# OSP_Carrier_V8_USB.net
KiCad netlist of a schematic drawn in Altium Designer
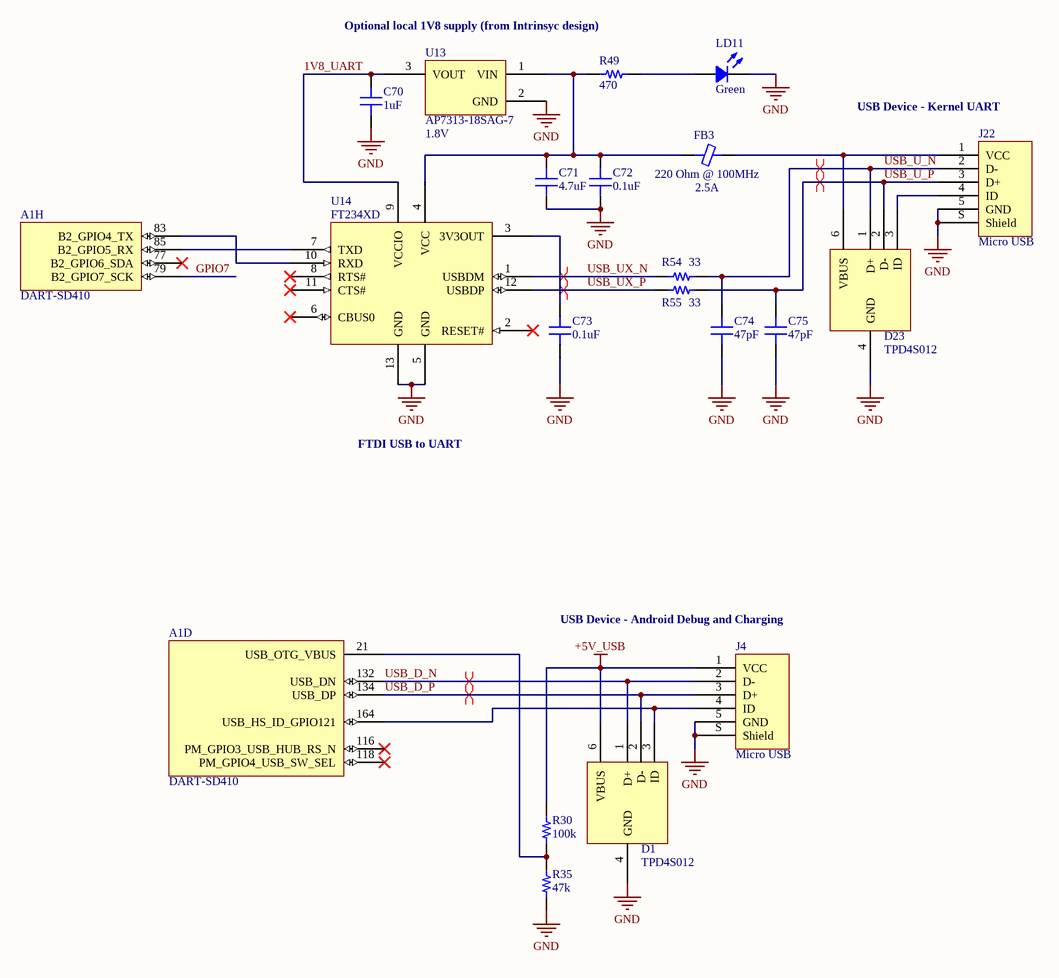
[diagram p0: OSP_Carrier_V8_USB.SchDoc]

(export (version "E")
  (design (tool "Eeschema 10.0.6"))
  (components
    (comp (ref "A1")
      (value "DART-SD410")
      (footprint "DART-SD410")
      (description "Variscite DART-SD410 System on Module")
      (libsource (lib "DART-SD410") (part "DART-SD410"))
    )
    (comp (ref "C70")
      (value "1uF")
      (footprint "CAP 0603/1608")
      (description "CAP CER 1UF 25V X7R 0603")
      (fields
        (field (name "PART NUMBER") "C1608X7R1E105K080AB")
        (field (name "MANUFACTURER") "TDK Corporation")
      )
      (libsource (lib "Celestial Library Database") (part "Capacitor"))
    )
    (comp (ref "C71")
      (value "4.7uF")
      (footprint "CAP 0402/1005")
      (description "CAP CER 4.7UF 10V X5R 0402")
      (fields
        (field (name "PART NUMBER") "C1005X5R1A475K050BC")
        (field (name "MANUFACTURER") "TDK Corporation")
      )
      (libsource (lib "Celestial Library Database") (part "Capacitor"))
    )
    (comp (ref "C72")
      (value "0.1uF")
      (footprint "CAP 0402/1005")
      (description "CAP CER 0.1UF 50V X7R 0402")
      (fields
        (field (name "PART NUMBER") "C1005X7R1H104K050BB")
        (field (name "MANUFACTURER") "TDK Corporation")
      )
      (libsource (lib "Celestial Library Database") (part "Capacitor"))
    )
    (comp (ref "C73")
      (value "0.1uF")
      (footprint "CAP 0402/1005")
      (description "CAP CER 0.1UF 50V X7R 0402")
      (fields
        (field (name "PART NUMBER") "C1005X7R1H104K050BB")
        (field (name "MANUFACTURER") "TDK Corporation")
      )
      (libsource (lib "Celestial Library Database") (part "Capacitor"))
    )
    (comp (ref "C74")
      (value "47pF")
      (footprint "CAP 0402/1005")
      (description "CAP CER 47PF 50V C0G 0402")
      (fields
        (field (name "PART NUMBER") "C1005C0G1H470G050BA")
        (field (name "MANUFACTURER") "TDK Corporation")
      )
      (libsource (lib "Celestial Library Database") (part "Capacitor"))
    )
    (comp (ref "C75")
      (value "47pF")
      (footprint "CAP 0402/1005")
      (description "CAP CER 47PF 50V C0G 0402")
      (fields
        (field (name "PART NUMBER") "C1005C0G1H470G050BA")
        (field (name "MANUFACTURER") "TDK Corporation")
      )
      (libsource (lib "Celestial Library Database") (part "Capacitor"))
    )
    (comp (ref "D1")
      (value "TPD4S012")
      (footprint "TI_SON6")
      (description "TI TPD4S012 USB ESD Protection")
      (libsource (lib "OSP_Symbols") (part "TI_TPD4S012"))
    )
    (comp (ref "D23")
      (value "TPD4S012")
      (footprint "TI_SON6")
      (description "TI TPD4S012 USB ESD Protection")
      (libsource (lib "OSP_Symbols") (part "TI_TPD4S012"))
    )
    (comp (ref "FB3")
      (value "220 Ohm @ 100MHz")
      (footprint "FER 0603/1608")
      (description "FERRITE CHIP 220 OHM 2500MA 0603")
      (fields
        (field (name "PART NUMBER") "CIS10P221NC")
        (field (name "MANUFACTURER") "Samsung Electro-Mechanics America, Inc.")
        (field (name "CURRENT RATING") "2.5A")
      )
      (libsource (lib "Celestial Library Database") (part "Ferrite Chip"))
    )
    (comp (ref "J4")
      (value "Micro USB")
      (footprint "FCI USB 10118193-0001LF")
      (description "CONN USB MICRO B RECPT SMT R/A")
      (fields (field (name "PART NUMBER") "10118193-0001LF"))
      (libsource (lib "Celestial Library Database") (part "USB 2.0 Type B Micro"))
    )
    (comp (ref "J22")
      (value "Micro USB")
      (footprint "FCI USB 10118193-0001LF")
      (description "CONN USB MICRO B RECPT SMT R/A")
      (fields (field (name "PART NUMBER") "10118193-0001LF"))
      (libsource (lib "Celestial Library Database") (part "USB 2.0 Type B Micro"))
    )
    (comp (ref "LD11")
      (value "Green")
      (footprint "LED 0603/1608 GREEN")
      (description "LED GREEN CLEAR 0603 SMD")
      (fields (field (name "PART NUMBER") "LTST-C191KGKT") (field (name "MANUFACTURER") "Lite-On Inc."))
      (libsource (lib "Celestial Library Database") (part "LED"))
    )
    (comp (ref "R30")
      (value "100k")
      (footprint "RES 0402/1005")
      (description "RES SMD 100K OHM 1% 1/10W 0402")
      (fields
        (field (name "PART NUMBER") "ERJ-2RKF1003X")
        (field (name "MANUFACTURER") "Panasonic Electronic Components")
      )
      (libsource (lib "Celestial Library Database") (part "Resistor"))
    )
    (comp (ref "R35")
      (value "47k")
      (footprint "RES 0402/1005")
      (description "RES SMD 47K OHM 1% 1/10W 0402")
      (fields
        (field (name "PART NUMBER") "ERJ-2RKF4702X")
        (field (name "MANUFACTURER") "Panasonic Electronic Components")
      )
      (libsource (lib "Celestial Library Database") (part "Resistor"))
    )
    (comp (ref "R49")
      (value "470")
      (footprint "RES 0402/1005")
      (description "RES SMD 470 OHM 1% 1/10W 0402")
      (fields
        (field (name "PART NUMBER") "ERJ-2RKF4700X")
        (field (name "MANUFACTURER") "Panasonic Electronic Components")
      )
      (libsource (lib "Celestial Library Database") (part "Resistor"))
    )
    (comp (ref "R54")
      (value "33")
      (footprint "RES 0402/1005")
      (description "RES SMD 33 OHM 1% 1/10W 0402")
      (fields
        (field (name "PART NUMBER") "ERJ-2RKF33R0X")
        (field (name "MANUFACTURER") "Panasonic Electronic Components")
      )
      (libsource (lib "Celestial Library Database") (part "Resistor"))
    )
    (comp (ref "R55")
      (value "33")
      (footprint "RES 0402/1005")
      (description "RES SMD 33 OHM 1% 1/10W 0402")
      (fields
        (field (name "PART NUMBER") "ERJ-2RKF33R0X")
        (field (name "MANUFACTURER") "Panasonic Electronic Components")
      )
      (libsource (lib "Celestial Library Database") (part "Resistor"))
    )
    (comp (ref "U13")
      (value "AP7313-18SAG-7")
      (footprint "DIODES SOT-23-3")
      (description "IC REG LDO 1.8V 0.15A SOT23-3")
      (fields (field (name "MANUFACTURER") "Diodes Incorporated") (field (name "VOLTAGE - OUTPUT") "1.8V"))
      (libsource (lib "Celestial Library Database") (part "Diodes Inc AP7313"))
    )
    (comp (ref "U14")
      (value "FT234XD")
      (footprint "FTDI_DFN12")
      (description "FTDI FT234XD USB to UART")
      (libsource (lib "OSP_Symbols") (part "FTDI_FT234XD"))
    )
  )
  (nets
    (net (code "1") (name "+5V_USB") (class "Default")
      (node (ref "D1") (pin "6") (pinfunction "VBUS_6") (pintype "passive"))
      (node (ref "J4") (pin "1") (pinfunction "VCC_1") (pintype "passive"))
      (node (ref "R30") (pin "2") (pinfunction "2_2") (pintype "passive"))
    )
    (net (code "2") (name "/1V8_UART") (class "Default")
      (node (ref "C70") (pin "2") (pinfunction "2_2") (pintype "passive"))
      (node (ref "U13") (pin "3") (pinfunction "VOUT_3") (pintype "passive"))
      (node (ref "U14") (pin "9") (pinfunction "VCCIO_9") (pintype "power_in"))
    )
    (net (code "3") (name "/GPIO7") (class "Default")
      (node (ref "A1") (pin "79") (pinfunction "B2_GPIO7_SCK_79") (pintype "bidirectional"))
    )
    (net (code "4") (name "/USB_D_N") (class "Default")
      (node (ref "A1") (pin "132") (pinfunction "USB_DN_132") (pintype "bidirectional"))
      (node (ref "D1") (pin "1") (pinfunction "D+_1") (pintype "passive"))
      (node (ref "J4") (pin "2") (pinfunction "D-_2") (pintype "passive"))
    )
    (net (code "5") (name "/USB_D_P") (class "Default")
      (node (ref "A1") (pin "134") (pinfunction "USB_DP_134") (pintype "bidirectional"))
      (node (ref "D1") (pin "2") (pinfunction "D-_2") (pintype "passive"))
      (node (ref "J4") (pin "3") (pinfunction "D+_3") (pintype "passive"))
    )
    (net (code "6") (name "/USB_UX_N") (class "Default")
      (node (ref "R54") (pin "1") (pinfunction "1_1") (pintype "passive"))
      (node (ref "U14") (pin "1") (pinfunction "USBDM_1") (pintype "bidirectional"))
    )
    (net (code "7") (name "/USB_UX_P") (class "Default")
      (node (ref "R55") (pin "1") (pinfunction "1_1") (pintype "passive"))
      (node (ref "U14") (pin "12") (pinfunction "USBDP_12") (pintype "bidirectional"))
    )
    (net (code "8") (name "/USB_U_N") (class "Default")
      (node (ref "C74") (pin "2") (pinfunction "2_2") (pintype "passive"))
      (node (ref "D23") (pin "1") (pinfunction "D+_1") (pintype "passive"))
      (node (ref "J22") (pin "2") (pinfunction "D-_2") (pintype "passive"))
      (node (ref "R54") (pin "2") (pinfunction "2_2") (pintype "passive"))
    )
    (net (code "9") (name "/USB_U_P") (class "Default")
      (node (ref "C75") (pin "2") (pinfunction "2_2") (pintype "passive"))
      (node (ref "D23") (pin "2") (pinfunction "D-_2") (pintype "passive"))
      (node (ref "J22") (pin "3") (pinfunction "D+_3") (pintype "passive"))
      (node (ref "R55") (pin "2") (pinfunction "2_2") (pintype "passive"))
    )
    (net (code "10") (name "GND") (class "Default")
      (node (ref "C70") (pin "1") (pinfunction "1_1") (pintype "passive"))
      (node (ref "C71") (pin "1") (pinfunction "1_1") (pintype "passive"))
      (node (ref "C72") (pin "1") (pinfunction "1_1") (pintype "passive"))
      (node (ref "C73") (pin "1") (pinfunction "1_1") (pintype "passive"))
      (node (ref "C74") (pin "1") (pinfunction "1_1") (pintype "passive"))
      (node (ref "C75") (pin "1") (pinfunction "1_1") (pintype "passive"))
      (node (ref "D1") (pin "4") (pinfunction "GND_4") (pintype "passive"))
      (node (ref "D23") (pin "4") (pinfunction "GND_4") (pintype "passive"))
      (node (ref "J22") (pin "5") (pinfunction "GND_5") (pintype "passive"))
      (node (ref "J22") (pin "S") (pinfunction "Shield_S") (pintype "passive"))
      (node (ref "J4") (pin "5") (pinfunction "GND_5") (pintype "passive"))
      (node (ref "J4") (pin "S") (pinfunction "Shield_S") (pintype "passive"))
      (node (ref "LD11") (pin "2") (pinfunction "2_2") (pintype "passive"))
      (node (ref "R35") (pin "1") (pinfunction "1_1") (pintype "passive"))
      (node (ref "U13") (pin "2") (pinfunction "GND_2") (pintype "passive"))
      (node (ref "U14") (pin "13") (pinfunction "GND_13") (pintype "power_in"))
      (node (ref "U14") (pin "5") (pinfunction "GND_5") (pintype "power_in"))
    )
    (net (code "11") (name "Net-(A1D-USB_HS_ID_GPIO121)") (class "Default")
      (node (ref "A1") (pin "164") (pinfunction "USB_HS_ID_GPIO121_164") (pintype "bidirectional"))
      (node (ref "D1") (pin "3") (pinfunction "ID_3") (pintype "passive"))
      (node (ref "J4") (pin "4") (pinfunction "ID_4") (pintype "passive"))
    )
    (net (code "12") (name "Net-(A1D-USB_OTG_VBUS)") (class "Default")
      (node (ref "A1") (pin "21") (pinfunction "USB_OTG_VBUS_21") (pintype "power_in"))
      (node (ref "R30") (pin "1") (pinfunction "1_1") (pintype "passive"))
      (node (ref "R35") (pin "2") (pinfunction "2_2") (pintype "passive"))
    )
    (net (code "13") (name "Net-(A1H-B2_GPIO4_TX)") (class "Default")
      (node (ref "A1") (pin "83") (pinfunction "B2_GPIO4_TX_83") (pintype "bidirectional"))
      (node (ref "U14") (pin "10") (pinfunction "RXD_10") (pintype "input"))
    )
    (net (code "14") (name "Net-(A1H-B2_GPIO5_RX)") (class "Default")
      (node (ref "A1") (pin "85") (pinfunction "B2_GPIO5_RX_85") (pintype "bidirectional"))
      (node (ref "U14") (pin "7") (pinfunction "TXD_7") (pintype "output"))
    )
    (net (code "15") (name "Net-(D23-ID)") (class "Default")
      (node (ref "D23") (pin "3") (pinfunction "ID_3") (pintype "passive"))
      (node (ref "J22") (pin "4") (pinfunction "ID_4") (pintype "passive"))
    )
    (net (code "16") (name "Net-(D23-VBUS)") (class "Default")
      (node (ref "D23") (pin "6") (pinfunction "VBUS_6") (pintype "passive"))
      (node (ref "FB3") (pin "2") (pinfunction "2_2") (pintype "passive"))
      (node (ref "J22") (pin "1") (pinfunction "VCC_1") (pintype "passive"))
    )
    (net (code "17") (name "Net-(LD11-Pad1)") (class "Default")
      (node (ref "LD11") (pin "1") (pinfunction "1_1") (pintype "passive"))
      (node (ref "R49") (pin "2") (pinfunction "2_2") (pintype "passive"))
    )
    (net (code "18") (name "Net-(U13-VIN)") (class "Default")
      (node (ref "C71") (pin "2") (pinfunction "2_2") (pintype "passive"))
      (node (ref "C72") (pin "2") (pinfunction "2_2") (pintype "passive"))
      (node (ref "FB3") (pin "1") (pinfunction "1_1") (pintype "passive"))
      (node (ref "R49") (pin "1") (pinfunction "1_1") (pintype "passive"))
      (node (ref "U13") (pin "1") (pinfunction "VIN_1") (pintype "passive"))
      (node (ref "U14") (pin "4") (pinfunction "VCC_4") (pintype "power_in"))
    )
    (net (code "19") (name "Net-(U14-3V3OUT)") (class "Default")
      (node (ref "C73") (pin "2") (pinfunction "2_2") (pintype "passive"))
      (node (ref "U14") (pin "3") (pinfunction "3V3OUT_3") (pintype "power_in"))
    )
    (net (code "20") (name "unconnected-(A1D-PM_GPIO3_USB_HUB_RS_N-Pad116)") (class "Default")
      (node (ref "A1") (pin "116") (pinfunction "PM_GPIO3_USB_HUB_RS_N_116") (pintype "bidirectional+no_connect"))
    )
    (net (code "21") (name "unconnected-(A1D-PM_GPIO4_USB_SW_SEL-Pad118)") (class "Default")
      (node (ref "A1") (pin "118") (pinfunction "PM_GPIO4_USB_SW_SEL_118") (pintype "bidirectional+no_connect"))
    )
    (net (code "22") (name "unconnected-(A1H-B2_GPIO6_SDA-Pad77)") (class "Default")
      (node (ref "A1") (pin "77") (pinfunction "B2_GPIO6_SDA_77") (pintype "bidirectional+no_connect"))
    )
    (net (code "23") (name "unconnected-(U14-CBUS0-Pad6)") (class "Default")
      (node (ref "U14") (pin "6") (pinfunction "CBUS0_6") (pintype "bidirectional+no_connect"))
    )
    (net (code "24") (name "unconnected-(U14-CTS#-Pad11)") (class "Default")
      (node (ref "U14") (pin "11") (pinfunction "CTS#_11") (pintype "input+no_connect"))
    )
    (net (code "25") (name "unconnected-(U14-RESET#-Pad2)") (class "Default")
      (node (ref "U14") (pin "2") (pinfunction "RESET#_2") (pintype "input+no_connect"))
    )
    (net (code "26") (name "unconnected-(U14-RTS#-Pad8)") (class "Default")
      (node (ref "U14") (pin "8") (pinfunction "RTS#_8") (pintype "output+no_connect"))
    )
  )
)
